# scoreboard_b2_v2.net
KiCad netlist of a schematic drawn in EAGLE
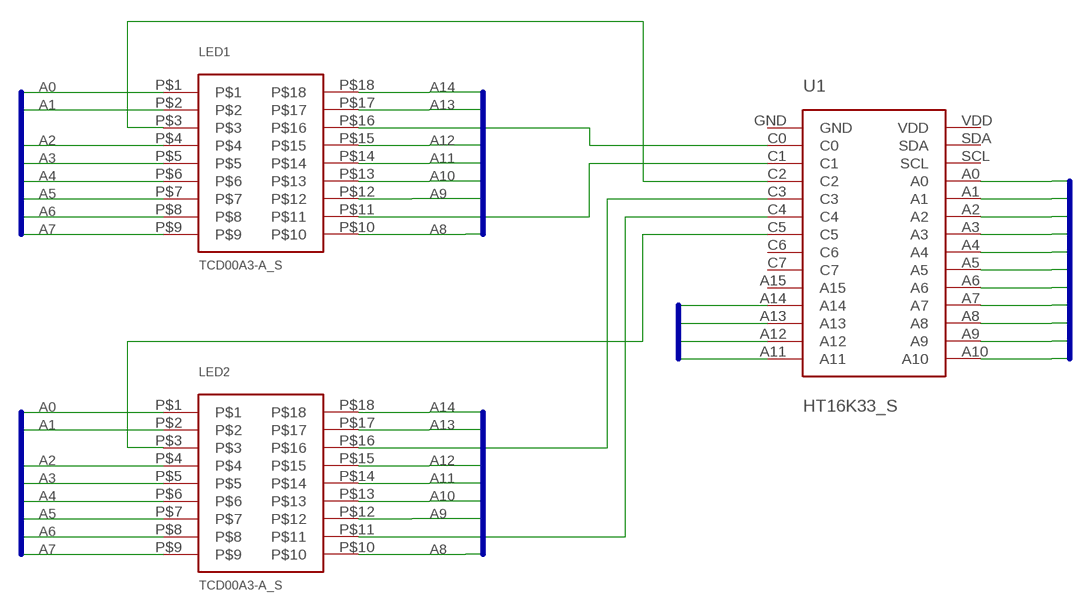
[diagram p0: schematic, sheet 1]

(export (version "E")
  (design (tool "Eeschema 10.0.6"))
  (components
    (comp (ref "LED1")
      (value "TCD00A3-A_S")
      (footprint "eagle-import:TCD00A3-A")
      (libsource (lib "eagle-import") (part "TCD00A3-A_S"))
    )
    (comp (ref "LED2")
      (value "TCD00A3-A_S")
      (footprint "eagle-import:TCD00A3-A")
      (libsource (lib "eagle-import") (part "TCD00A3-A_S"))
    )
    (comp (ref "U1")
      (value "HT16K33_S")
      (footprint "eagle-import:HT16K33")
      (libsource (lib "eagle-import") (part "HT16K33_S"))
    )
  )
  (nets
    (net (code "1") (name "/A0") (class "Default")
      (node (ref "LED1") (pin "P$1") (pinfunction "P$1_P$1") (pintype "bidirectional"))
      (node (ref "LED2") (pin "P$1") (pinfunction "P$1_P$1") (pintype "bidirectional"))
      (node (ref "U1") (pin "A0") (pinfunction "A0_A0") (pintype "bidirectional"))
    )
    (net (code "2") (name "/A1") (class "Default")
      (node (ref "LED1") (pin "P$2") (pinfunction "P$2_P$2") (pintype "bidirectional"))
      (node (ref "LED2") (pin "P$2") (pinfunction "P$2_P$2") (pintype "bidirectional"))
      (node (ref "U1") (pin "A1") (pinfunction "A1_A1") (pintype "bidirectional"))
    )
    (net (code "3") (name "/A2") (class "Default")
      (node (ref "LED1") (pin "P$4") (pinfunction "P$4_P$4") (pintype "bidirectional"))
      (node (ref "LED2") (pin "P$4") (pinfunction "P$4_P$4") (pintype "bidirectional"))
      (node (ref "U1") (pin "A2") (pinfunction "A2_A2") (pintype "bidirectional"))
    )
    (net (code "4") (name "/A3") (class "Default")
      (node (ref "LED1") (pin "P$5") (pinfunction "P$5_P$5") (pintype "bidirectional"))
      (node (ref "LED2") (pin "P$5") (pinfunction "P$5_P$5") (pintype "bidirectional"))
      (node (ref "U1") (pin "A3") (pinfunction "A3_A3") (pintype "bidirectional"))
    )
    (net (code "5") (name "/A4") (class "Default")
      (node (ref "LED1") (pin "P$6") (pinfunction "P$6_P$6") (pintype "bidirectional"))
      (node (ref "LED2") (pin "P$6") (pinfunction "P$6_P$6") (pintype "bidirectional"))
      (node (ref "U1") (pin "A4") (pinfunction "A4_A4") (pintype "bidirectional"))
    )
    (net (code "6") (name "/A5") (class "Default")
      (node (ref "LED1") (pin "P$7") (pinfunction "P$7_P$7") (pintype "bidirectional"))
      (node (ref "LED2") (pin "P$7") (pinfunction "P$7_P$7") (pintype "bidirectional"))
      (node (ref "U1") (pin "A5") (pinfunction "A5_A5") (pintype "bidirectional"))
    )
    (net (code "7") (name "/A6") (class "Default")
      (node (ref "LED1") (pin "P$8") (pinfunction "P$8_P$8") (pintype "bidirectional"))
      (node (ref "LED2") (pin "P$8") (pinfunction "P$8_P$8") (pintype "bidirectional"))
      (node (ref "U1") (pin "A6") (pinfunction "A6_A6") (pintype "bidirectional"))
    )
    (net (code "8") (name "/A7") (class "Default")
      (node (ref "LED1") (pin "P$9") (pinfunction "P$9_P$9") (pintype "bidirectional"))
      (node (ref "LED2") (pin "P$9") (pinfunction "P$9_P$9") (pintype "bidirectional"))
      (node (ref "U1") (pin "A7") (pinfunction "A7_A7") (pintype "bidirectional"))
    )
    (net (code "9") (name "/A8") (class "Default")
      (node (ref "LED1") (pin "P$10") (pinfunction "P$10_P$10") (pintype "bidirectional"))
      (node (ref "LED2") (pin "P$10") (pinfunction "P$10_P$10") (pintype "bidirectional"))
      (node (ref "U1") (pin "A8") (pinfunction "A8_A8") (pintype "bidirectional"))
    )
    (net (code "10") (name "/A9") (class "Default")
      (node (ref "LED1") (pin "P$12") (pinfunction "P$12_P$12") (pintype "bidirectional"))
      (node (ref "LED2") (pin "P$12") (pinfunction "P$12_P$12") (pintype "bidirectional"))
      (node (ref "U1") (pin "A9") (pinfunction "A9_A9") (pintype "bidirectional"))
    )
    (net (code "11") (name "/A10") (class "Default")
      (node (ref "LED1") (pin "P$13") (pinfunction "P$13_P$13") (pintype "bidirectional"))
      (node (ref "LED2") (pin "P$13") (pinfunction "P$13_P$13") (pintype "bidirectional"))
      (node (ref "U1") (pin "A10") (pinfunction "A10_A10") (pintype "bidirectional"))
    )
    (net (code "12") (name "/A11") (class "Default")
      (node (ref "LED1") (pin "P$14") (pinfunction "P$14_P$14") (pintype "bidirectional"))
      (node (ref "LED2") (pin "P$14") (pinfunction "P$14_P$14") (pintype "bidirectional"))
      (node (ref "U1") (pin "A11") (pinfunction "A11_A11") (pintype "bidirectional"))
    )
    (net (code "13") (name "/A12") (class "Default")
      (node (ref "LED1") (pin "P$15") (pinfunction "P$15_P$15") (pintype "bidirectional"))
      (node (ref "LED2") (pin "P$15") (pinfunction "P$15_P$15") (pintype "bidirectional"))
      (node (ref "U1") (pin "A12") (pinfunction "A12_A12") (pintype "bidirectional"))
    )
    (net (code "14") (name "/A13") (class "Default")
      (node (ref "LED1") (pin "P$17") (pinfunction "P$17_P$17") (pintype "bidirectional"))
      (node (ref "LED2") (pin "P$17") (pinfunction "P$17_P$17") (pintype "bidirectional"))
      (node (ref "U1") (pin "A13") (pinfunction "A13_A13") (pintype "bidirectional"))
    )
    (net (code "15") (name "/A14") (class "Default")
      (node (ref "LED1") (pin "P$18") (pinfunction "P$18_P$18") (pintype "bidirectional"))
      (node (ref "LED2") (pin "P$18") (pinfunction "P$18_P$18") (pintype "bidirectional"))
      (node (ref "U1") (pin "A14") (pinfunction "A14_A14") (pintype "bidirectional"))
    )
    (net (code "16") (name "Net-(LED1-PadP$3)") (class "Default")
      (node (ref "LED1") (pin "P$3") (pinfunction "P$3_P$3") (pintype "bidirectional"))
      (node (ref "U1") (pin "C2") (pinfunction "C2_C2") (pintype "bidirectional"))
    )
    (net (code "17") (name "Net-(LED1-PadP$11)") (class "Default")
      (node (ref "LED1") (pin "P$11") (pinfunction "P$11_P$11") (pintype "bidirectional"))
      (node (ref "U1") (pin "C1") (pinfunction "C1_C1") (pintype "bidirectional"))
    )
    (net (code "18") (name "Net-(LED1-PadP$16)") (class "Default")
      (node (ref "LED1") (pin "P$16") (pinfunction "P$16_P$16") (pintype "bidirectional"))
      (node (ref "U1") (pin "C0") (pinfunction "C0_C0") (pintype "bidirectional"))
    )
    (net (code "19") (name "Net-(LED2-PadP$3)") (class "Default")
      (node (ref "LED2") (pin "P$3") (pinfunction "P$3_P$3") (pintype "bidirectional"))
      (node (ref "U1") (pin "C5") (pinfunction "C5_C5") (pintype "bidirectional"))
    )
    (net (code "20") (name "Net-(LED2-PadP$11)") (class "Default")
      (node (ref "LED2") (pin "P$11") (pinfunction "P$11_P$11") (pintype "bidirectional"))
      (node (ref "U1") (pin "C4") (pinfunction "C4_C4") (pintype "bidirectional"))
    )
    (net (code "21") (name "Net-(LED2-PadP$16)") (class "Default")
      (node (ref "LED2") (pin "P$16") (pinfunction "P$16_P$16") (pintype "bidirectional"))
      (node (ref "U1") (pin "C3") (pinfunction "C3_C3") (pintype "bidirectional"))
    )
    (net (code "22") (name "unconnected-(U1-PadA15)") (class "Default")
      (node (ref "U1") (pin "A15") (pinfunction "A15_A15") (pintype "bidirectional"))
    )
    (net (code "23") (name "unconnected-(U1-PadC6)") (class "Default")
      (node (ref "U1") (pin "C6") (pinfunction "C6_C6") (pintype "bidirectional"))
    )
    (net (code "24") (name "unconnected-(U1-PadC7)") (class "Default")
      (node (ref "U1") (pin "C7") (pinfunction "C7_C7") (pintype "bidirectional"))
    )
    (net (code "25") (name "unconnected-(U1-PadGND)") (class "Default")
      (node (ref "U1") (pin "GND") (pinfunction "GND_GND") (pintype "bidirectional"))
    )
    (net (code "26") (name "unconnected-(U1-PadSCL)") (class "Default")
      (node (ref "U1") (pin "SCL") (pinfunction "SCL_SCL") (pintype "bidirectional"))
    )
    (net (code "27") (name "unconnected-(U1-PadSDA)") (class "Default")
      (node (ref "U1") (pin "SDA") (pinfunction "SDA_SDA") (pintype "bidirectional"))
    )
    (net (code "28") (name "unconnected-(U1-PadVDD)") (class "Default")
      (node (ref "U1") (pin "VDD") (pinfunction "VDD_VDD") (pintype "bidirectional"))
    )
  )
)
